# Memoria.net
KiCad netlist of a schematic drawn in Altium Designer
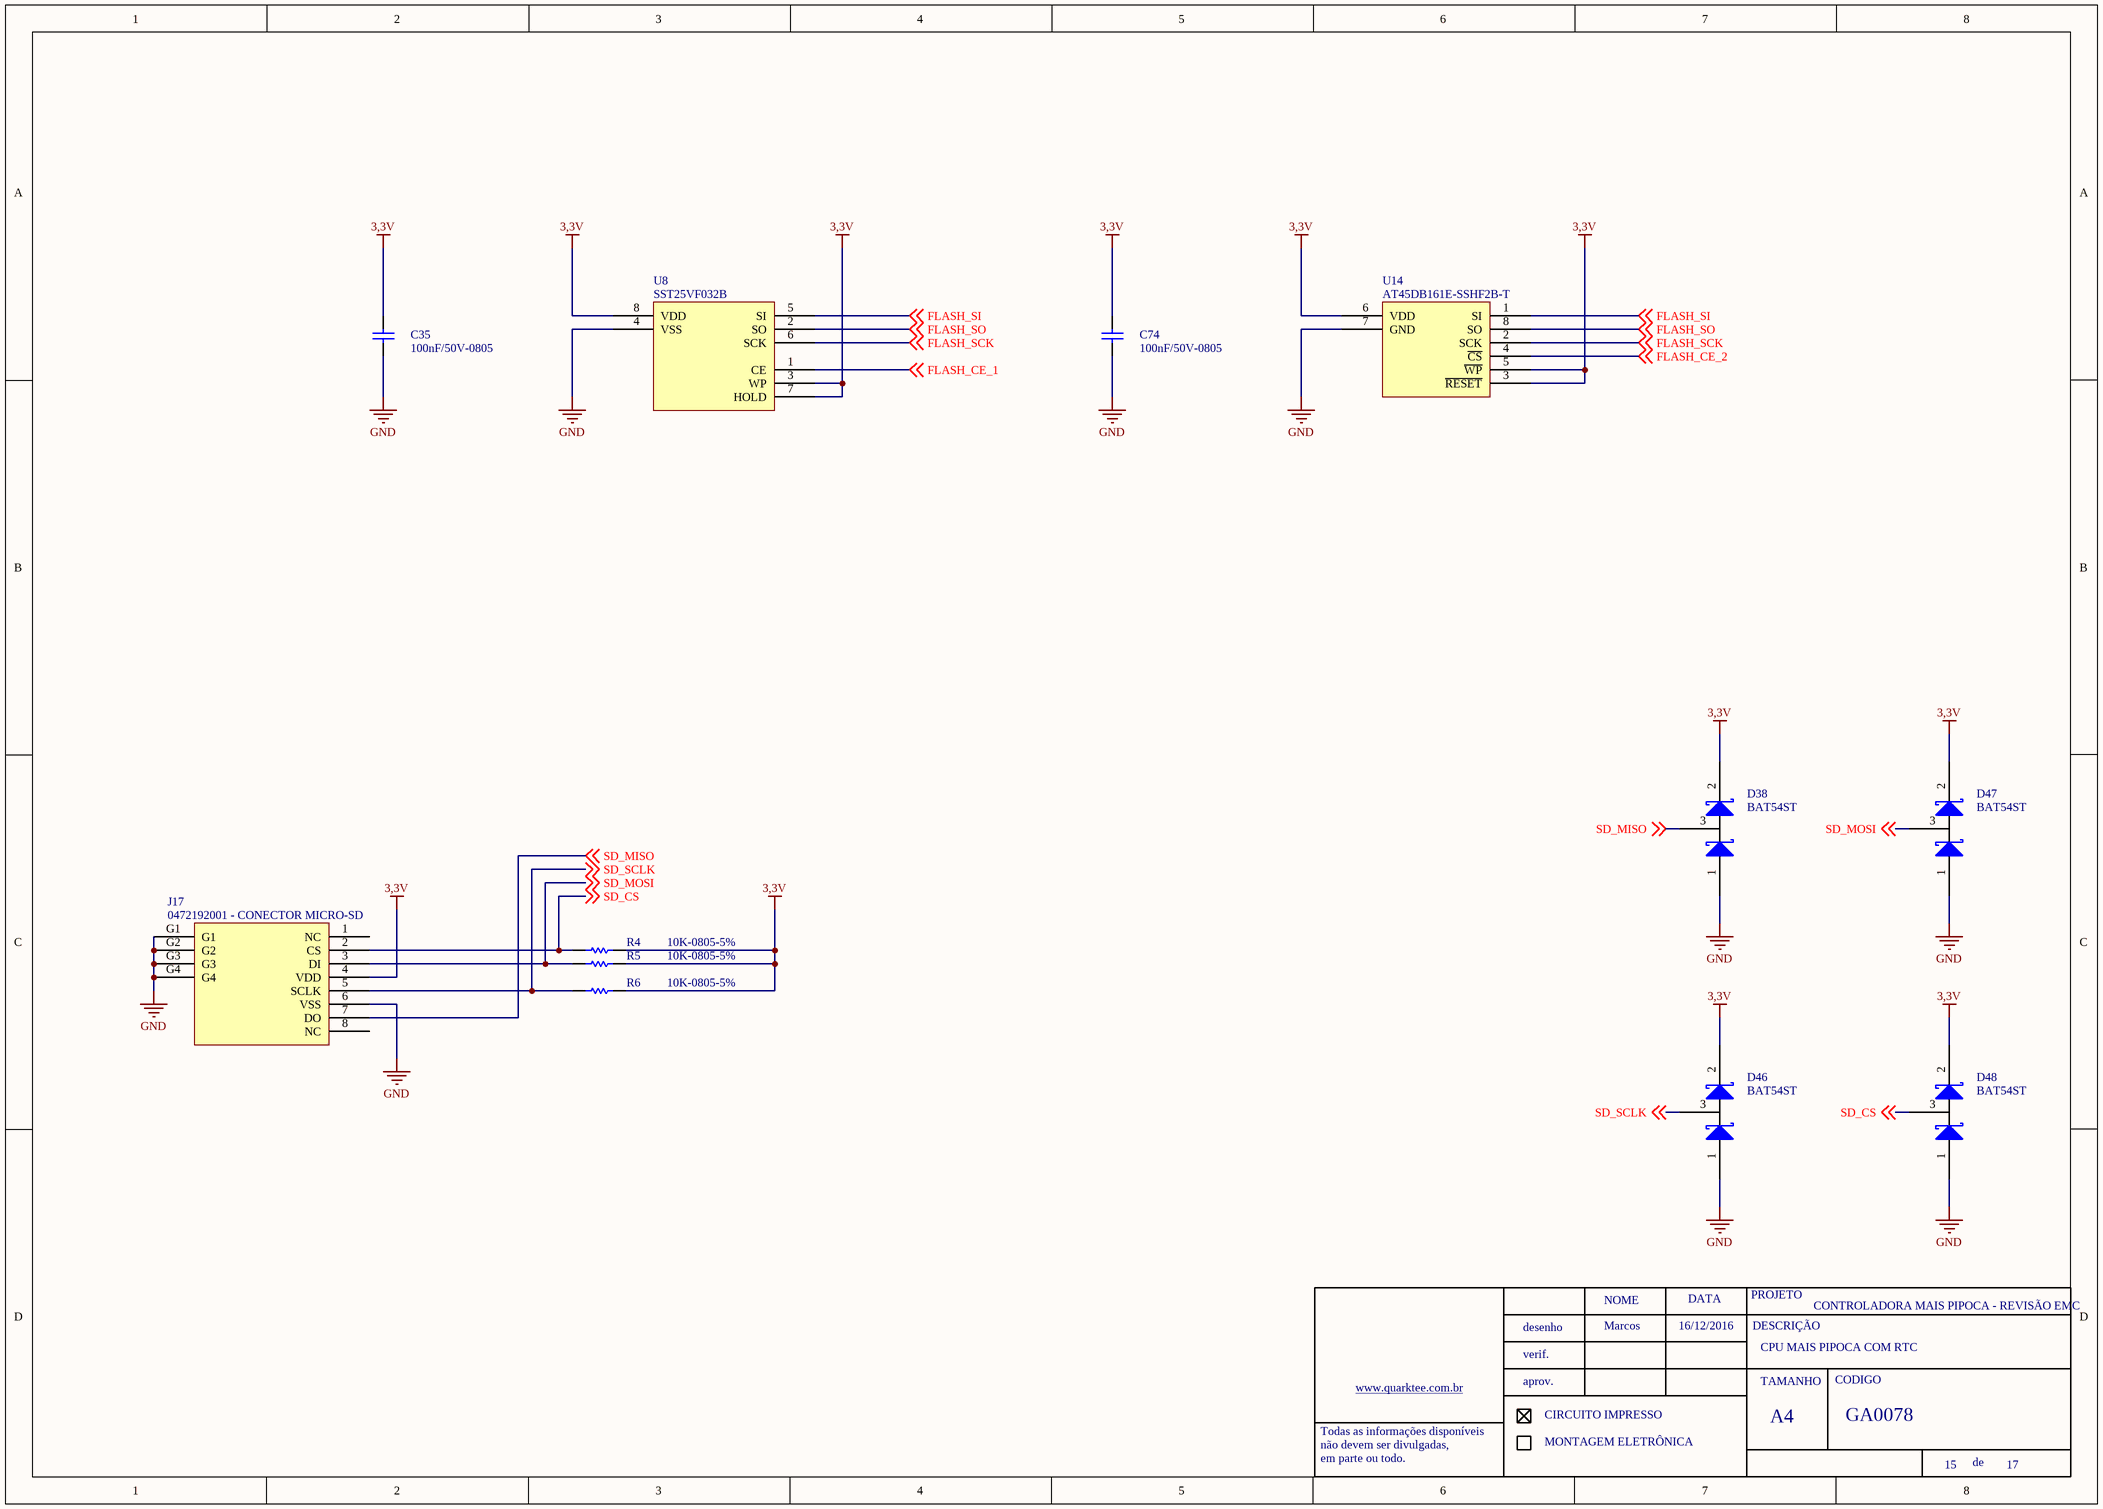
[diagram p0: Memoria.SchDoc]

(export (version "E")
  (design (tool "Eeschema 10.0.6"))
  (components
    (comp (ref "C35")
      (value "100nF/50V-0805")
      (footprint "0805-REVISADO ONDA")
      (description "100nF/50-0805-NPO")
      (libsource (lib "AquinoLib") (part "100nF/50-0805-NPO"))
    )
    (comp (ref "C74")
      (value "100nF/50V-0805")
      (footprint "0805-REVISADO ONDA")
      (description "100nF/50-0805-NPO")
      (libsource (lib "AquinoLib") (part "100nF/50-0805-NPO"))
    )
    (comp (ref "D38")
      (value "BAT54ST")
      (footprint "SOT23 - REVISADO ONDA")
      (libsource (lib "AquinoLib") (part "BAT54ST"))
    )
    (comp (ref "D46")
      (value "BAT54ST")
      (footprint "SOT23 - REVISADO ONDA")
      (libsource (lib "AquinoLib") (part "BAT54ST"))
    )
    (comp (ref "D47")
      (value "BAT54ST")
      (footprint "SOT23 - REVISADO ONDA")
      (libsource (lib "AquinoLib") (part "BAT54ST"))
    )
    (comp (ref "D48")
      (value "BAT54ST")
      (footprint "SOT23 - REVISADO ONDA")
      (libsource (lib "AquinoLib") (part "BAT54ST"))
    )
    (comp (ref "J17")
      (value "0472192001 - CONECTOR MICRO-SD")
      (libsource (lib "AquinoLib") (part "CONECTOR MICRO-SD"))
    )
    (comp (ref "R4")
      (value "10K-0805-5%")
      (footprint "0805-REVISADO ONDA")
      (libsource (lib "AquinoLib") (part "10K-0805-5%"))
    )
    (comp (ref "R5")
      (value "10K-0805-5%")
      (footprint "0805-REVISADO ONDA")
      (libsource (lib "AquinoLib") (part "10K-0805-5%"))
    )
    (comp (ref "R6")
      (value "10K-0805-5%")
      (footprint "0805-REVISADO ONDA")
      (libsource (lib "AquinoLib") (part "10K-0805-5%"))
    )
    (comp (ref "U8")
      (value "SST25VF032B")
      (footprint "SOIC LARGO ATMEL")
      (libsource (lib "ChaveDigital3") (part "SST25VF032B"))
    )
    (comp (ref "U14")
      (value "AT45DB161E-SSHF2B-T")
      (libsource (lib "AquinoLib") (part "AT45DB161E-SSHF2B-T"))
    )
  )
  (nets
    (net (code "1") (name "3,3V") (class "Default")
      (node (ref "C35") (pin "2") (pinfunction "2_2") (pintype "passive"))
      (node (ref "C74") (pin "2") (pinfunction "2_2") (pintype "passive"))
      (node (ref "D38") (pin "2") (pinfunction "2_2") (pintype "passive"))
      (node (ref "D46") (pin "2") (pinfunction "2_2") (pintype "passive"))
      (node (ref "D47") (pin "2") (pinfunction "2_2") (pintype "passive"))
      (node (ref "D48") (pin "2") (pinfunction "2_2") (pintype "passive"))
      (node (ref "J17") (pin "4") (pinfunction "VDD_4") (pintype "passive"))
      (node (ref "R4") (pin "1") (pinfunction "1_1") (pintype "passive"))
      (node (ref "R5") (pin "1") (pinfunction "1_1") (pintype "passive"))
      (node (ref "R6") (pin "1") (pinfunction "1_1") (pintype "passive"))
      (node (ref "U14") (pin "3") (pinfunction "~{RESET}_3") (pintype "passive"))
      (node (ref "U14") (pin "5") (pinfunction "~{WP}_5") (pintype "passive"))
      (node (ref "U14") (pin "6") (pinfunction "VDD_6") (pintype "passive"))
      (node (ref "U8") (pin "3") (pinfunction "WP_3") (pintype "passive"))
      (node (ref "U8") (pin "7") (pinfunction "HOLD_7") (pintype "passive"))
      (node (ref "U8") (pin "8") (pinfunction "VDD_8") (pintype "passive"))
    )
    (net (code "2") (name "FLASH_CE_1") (class "Default")
      (node (ref "U8") (pin "1") (pinfunction "CE_1") (pintype "passive"))
    )
    (net (code "3") (name "FLASH_CE_2") (class "Default")
      (node (ref "U14") (pin "4") (pinfunction "~{CS}_4") (pintype "passive"))
    )
    (net (code "4") (name "FLASH_SCK") (class "Default")
      (node (ref "U14") (pin "2") (pinfunction "SCK_2") (pintype "passive"))
      (node (ref "U8") (pin "6") (pinfunction "SCK_6") (pintype "passive"))
    )
    (net (code "5") (name "FLASH_SI") (class "Default")
      (node (ref "U14") (pin "1") (pinfunction "SI_1") (pintype "passive"))
      (node (ref "U8") (pin "5") (pinfunction "SI_5") (pintype "passive"))
    )
    (net (code "6") (name "FLASH_SO") (class "Default")
      (node (ref "U14") (pin "8") (pinfunction "SO_8") (pintype "passive"))
      (node (ref "U8") (pin "2") (pinfunction "SO_2") (pintype "passive"))
    )
    (net (code "7") (name "GND") (class "Default")
      (node (ref "C35") (pin "1") (pinfunction "1_1") (pintype "passive"))
      (node (ref "C74") (pin "1") (pinfunction "1_1") (pintype "passive"))
      (node (ref "D38") (pin "1") (pinfunction "1_1") (pintype "passive"))
      (node (ref "D46") (pin "1") (pinfunction "1_1") (pintype "passive"))
      (node (ref "D47") (pin "1") (pinfunction "1_1") (pintype "passive"))
      (node (ref "D48") (pin "1") (pinfunction "1_1") (pintype "passive"))
      (node (ref "J17") (pin "6") (pinfunction "VSS_6") (pintype "passive"))
      (node (ref "J17") (pin "G1") (pinfunction "G1_G1") (pintype "passive"))
      (node (ref "J17") (pin "G2") (pinfunction "G2_G2") (pintype "passive"))
      (node (ref "J17") (pin "G3") (pinfunction "G3_G3") (pintype "passive"))
      (node (ref "J17") (pin "G4") (pinfunction "G4_G4") (pintype "passive"))
      (node (ref "U14") (pin "7") (pinfunction "GND_7") (pintype "passive"))
      (node (ref "U8") (pin "4") (pinfunction "VSS_4") (pintype "passive"))
    )
    (net (code "8") (name "SD_CS") (class "Default")
      (node (ref "D48") (pin "3") (pinfunction "3_3") (pintype "passive"))
      (node (ref "J17") (pin "2") (pinfunction "CS_2") (pintype "passive"))
      (node (ref "R4") (pin "2") (pinfunction "2_2") (pintype "passive"))
    )
    (net (code "9") (name "SD_MISO") (class "Default")
      (node (ref "D38") (pin "3") (pinfunction "3_3") (pintype "passive"))
      (node (ref "J17") (pin "7") (pinfunction "DO_7") (pintype "passive"))
    )
    (net (code "10") (name "SD_MOSI") (class "Default")
      (node (ref "D47") (pin "3") (pinfunction "3_3") (pintype "passive"))
      (node (ref "J17") (pin "3") (pinfunction "DI_3") (pintype "passive"))
      (node (ref "R5") (pin "2") (pinfunction "2_2") (pintype "passive"))
    )
    (net (code "11") (name "SD_SCLK") (class "Default")
      (node (ref "D46") (pin "3") (pinfunction "3_3") (pintype "passive"))
      (node (ref "J17") (pin "5") (pinfunction "SCLK_5") (pintype "passive"))
      (node (ref "R6") (pin "2") (pinfunction "2_2") (pintype "passive"))
    )
    (net (code "12") (name "unconnected-(J17-NC-Pad1)") (class "Default")
      (node (ref "J17") (pin "1") (pinfunction "NC_1") (pintype "passive"))
    )
    (net (code "13") (name "unconnected-(J17-NC-Pad8)") (class "Default")
      (node (ref "J17") (pin "8") (pinfunction "NC_8") (pintype "passive"))
    )
  )
)
